# relays2.net
KiCad netlist of a schematic drawn in Altium Designer
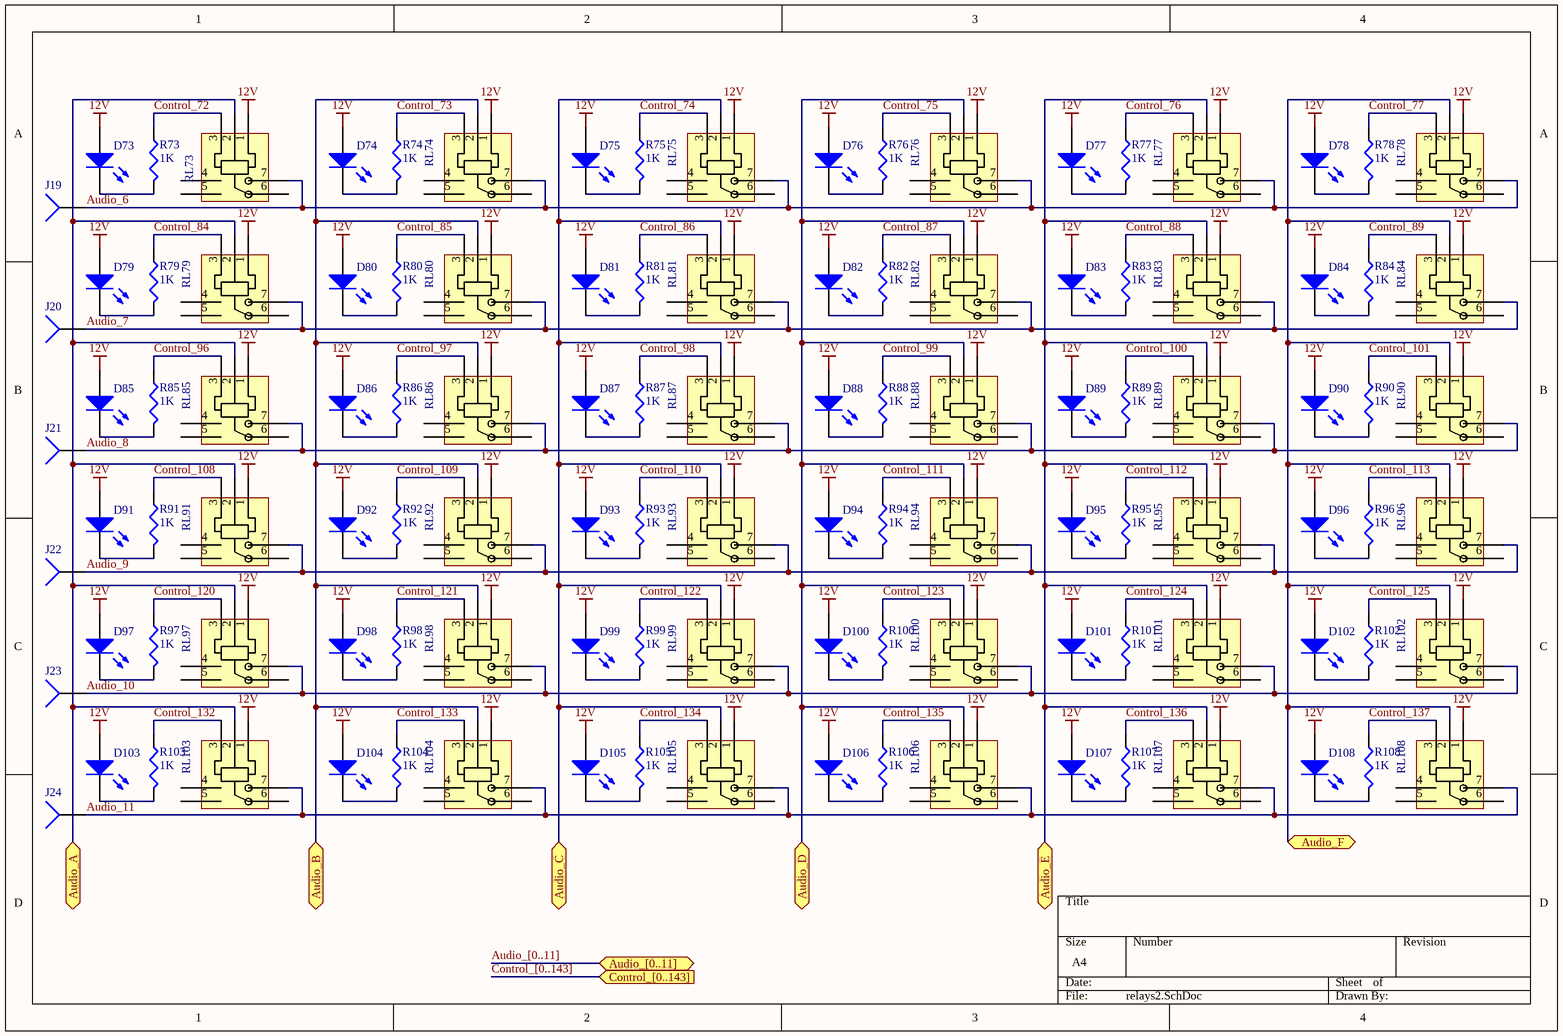
[diagram p0: relays2.SchDoc]

(export (version "E")
  (design (tool "Eeschema 10.0.6"))
  (components
    (comp (ref "D73")
      (value "LED0")
      (footprint "LED_round_5mm")
      (description "Typical INFRARED GaAs LED")
      (libsource (lib "Miscellaneous Devices") (part "LED0"))
    )
    (comp (ref "D74")
      (value "LED0")
      (footprint "LED_round_5mm")
      (description "Typical INFRARED GaAs LED")
      (libsource (lib "Miscellaneous Devices") (part "LED0"))
    )
    (comp (ref "D75")
      (value "LED0")
      (footprint "LED_round_5mm")
      (description "Typical INFRARED GaAs LED")
      (libsource (lib "Miscellaneous Devices") (part "LED0"))
    )
    (comp (ref "D76")
      (value "LED0")
      (footprint "LED_round_5mm")
      (description "Typical INFRARED GaAs LED")
      (libsource (lib "Miscellaneous Devices") (part "LED0"))
    )
    (comp (ref "D77")
      (value "LED0")
      (footprint "LED_round_5mm")
      (description "Typical INFRARED GaAs LED")
      (libsource (lib "Miscellaneous Devices") (part "LED0"))
    )
    (comp (ref "D78")
      (value "LED0")
      (footprint "LED_round_5mm")
      (description "Typical INFRARED GaAs LED")
      (libsource (lib "Miscellaneous Devices") (part "LED0"))
    )
    (comp (ref "D79")
      (value "LED0")
      (footprint "LED_round_5mm")
      (description "Typical INFRARED GaAs LED")
      (libsource (lib "Miscellaneous Devices") (part "LED0"))
    )
    (comp (ref "D80")
      (value "LED0")
      (footprint "LED_round_5mm")
      (description "Typical INFRARED GaAs LED")
      (libsource (lib "Miscellaneous Devices") (part "LED0"))
    )
    (comp (ref "D81")
      (value "LED0")
      (footprint "LED_round_5mm")
      (description "Typical INFRARED GaAs LED")
      (libsource (lib "Miscellaneous Devices") (part "LED0"))
    )
    (comp (ref "D82")
      (value "LED0")
      (footprint "LED_round_5mm")
      (description "Typical INFRARED GaAs LED")
      (libsource (lib "Miscellaneous Devices") (part "LED0"))
    )
    (comp (ref "D83")
      (value "LED0")
      (footprint "LED_round_5mm")
      (description "Typical INFRARED GaAs LED")
      (libsource (lib "Miscellaneous Devices") (part "LED0"))
    )
    (comp (ref "D84")
      (value "LED0")
      (footprint "LED_round_5mm")
      (description "Typical INFRARED GaAs LED")
      (libsource (lib "Miscellaneous Devices") (part "LED0"))
    )
    (comp (ref "D85")
      (value "LED0")
      (footprint "LED_round_5mm")
      (description "Typical INFRARED GaAs LED")
      (libsource (lib "Miscellaneous Devices") (part "LED0"))
    )
    (comp (ref "D86")
      (value "LED0")
      (footprint "LED_round_5mm")
      (description "Typical INFRARED GaAs LED")
      (libsource (lib "Miscellaneous Devices") (part "LED0"))
    )
    (comp (ref "D87")
      (value "LED0")
      (footprint "LED_round_5mm")
      (description "Typical INFRARED GaAs LED")
      (libsource (lib "Miscellaneous Devices") (part "LED0"))
    )
    (comp (ref "D88")
      (value "LED0")
      (footprint "LED_round_5mm")
      (description "Typical INFRARED GaAs LED")
      (libsource (lib "Miscellaneous Devices") (part "LED0"))
    )
    (comp (ref "D89")
      (value "LED0")
      (footprint "LED_round_5mm")
      (description "Typical INFRARED GaAs LED")
      (libsource (lib "Miscellaneous Devices") (part "LED0"))
    )
    (comp (ref "D90")
      (value "LED0")
      (footprint "LED_round_5mm")
      (description "Typical INFRARED GaAs LED")
      (libsource (lib "Miscellaneous Devices") (part "LED0"))
    )
    (comp (ref "D91")
      (value "LED0")
      (footprint "LED_round_5mm")
      (description "Typical INFRARED GaAs LED")
      (libsource (lib "Miscellaneous Devices") (part "LED0"))
    )
    (comp (ref "D92")
      (value "LED0")
      (footprint "LED_round_5mm")
      (description "Typical INFRARED GaAs LED")
      (libsource (lib "Miscellaneous Devices") (part "LED0"))
    )
    (comp (ref "D93")
      (value "LED0")
      (footprint "LED_round_5mm")
      (description "Typical INFRARED GaAs LED")
      (libsource (lib "Miscellaneous Devices") (part "LED0"))
    )
    (comp (ref "D94")
      (value "LED0")
      (footprint "LED_round_5mm")
      (description "Typical INFRARED GaAs LED")
      (libsource (lib "Miscellaneous Devices") (part "LED0"))
    )
    (comp (ref "D95")
      (value "LED0")
      (footprint "LED_round_5mm")
      (description "Typical INFRARED GaAs LED")
      (libsource (lib "Miscellaneous Devices") (part "LED0"))
    )
    (comp (ref "D96")
      (value "LED0")
      (footprint "LED_round_5mm")
      (description "Typical INFRARED GaAs LED")
      (libsource (lib "Miscellaneous Devices") (part "LED0"))
    )
    (comp (ref "D97")
      (value "LED0")
      (footprint "LED_round_5mm")
      (description "Typical INFRARED GaAs LED")
      (libsource (lib "Miscellaneous Devices") (part "LED0"))
    )
    (comp (ref "D98")
      (value "LED0")
      (footprint "LED_round_5mm")
      (description "Typical INFRARED GaAs LED")
      (libsource (lib "Miscellaneous Devices") (part "LED0"))
    )
    (comp (ref "D99")
      (value "LED0")
      (footprint "LED_round_5mm")
      (description "Typical INFRARED GaAs LED")
      (libsource (lib "Miscellaneous Devices") (part "LED0"))
    )
    (comp (ref "D100")
      (value "LED0")
      (footprint "LED_round_5mm")
      (description "Typical INFRARED GaAs LED")
      (libsource (lib "Miscellaneous Devices") (part "LED0"))
    )
    (comp (ref "D101")
      (value "LED0")
      (footprint "LED_round_5mm")
      (description "Typical INFRARED GaAs LED")
      (libsource (lib "Miscellaneous Devices") (part "LED0"))
    )
    (comp (ref "D102")
      (value "LED0")
      (footprint "LED_round_5mm")
      (description "Typical INFRARED GaAs LED")
      (libsource (lib "Miscellaneous Devices") (part "LED0"))
    )
    (comp (ref "D103")
      (value "LED0")
      (footprint "LED_round_5mm")
      (description "Typical INFRARED GaAs LED")
      (libsource (lib "Miscellaneous Devices") (part "LED0"))
    )
    (comp (ref "D104")
      (value "LED0")
      (footprint "LED_round_5mm")
      (description "Typical INFRARED GaAs LED")
      (libsource (lib "Miscellaneous Devices") (part "LED0"))
    )
    (comp (ref "D105")
      (value "LED0")
      (footprint "LED_round_5mm")
      (description "Typical INFRARED GaAs LED")
      (libsource (lib "Miscellaneous Devices") (part "LED0"))
    )
    (comp (ref "D106")
      (value "LED0")
      (footprint "LED_round_5mm")
      (description "Typical INFRARED GaAs LED")
      (libsource (lib "Miscellaneous Devices") (part "LED0"))
    )
    (comp (ref "D107")
      (value "LED0")
      (footprint "LED_round_5mm")
      (description "Typical INFRARED GaAs LED")
      (libsource (lib "Miscellaneous Devices") (part "LED0"))
    )
    (comp (ref "D108")
      (value "LED0")
      (footprint "LED_round_5mm")
      (description "Typical INFRARED GaAs LED")
      (libsource (lib "Miscellaneous Devices") (part "LED0"))
    )
    (comp (ref "J19")
      (value "Audio")
      (footprint "Conn_1_2x4")
      (description "Socket")
      (libsource (lib "Miscellaneous Connectors") (part "Socket"))
    )
    (comp (ref "J20")
      (value "Audio")
      (footprint "Conn_1_2x4")
      (description "Socket")
      (libsource (lib "Miscellaneous Connectors") (part "Socket"))
    )
    (comp (ref "J21")
      (value "Audio")
      (footprint "Conn_1_2x4")
      (description "Socket")
      (libsource (lib "Miscellaneous Connectors") (part "Socket"))
    )
    (comp (ref "J22")
      (value "Audio")
      (footprint "Conn_1_2x4")
      (description "Socket")
      (libsource (lib "Miscellaneous Connectors") (part "Socket"))
    )
    (comp (ref "J23")
      (value "Audio")
      (footprint "Conn_1_2x4")
      (description "Socket")
      (libsource (lib "Miscellaneous Connectors") (part "Socket"))
    )
    (comp (ref "J24")
      (value "Audio")
      (footprint "Conn_1_2x4")
      (description "Socket")
      (libsource (lib "Miscellaneous Connectors") (part "Socket"))
    )
    (comp (ref "R73")
      (value "1K")
      (footprint "J1-0603")
      (description "Resistor")
      (fields (field (name "Comment") "Res3"))
      (libsource (lib "Miscellaneous Devices") (part "Res3"))
    )
    (comp (ref "R74")
      (value "1K")
      (footprint "J1-0603")
      (description "Resistor")
      (fields (field (name "Comment") "Res3"))
      (libsource (lib "Miscellaneous Devices") (part "Res3"))
    )
    (comp (ref "R75")
      (value "1K")
      (footprint "J1-0603")
      (description "Resistor")
      (fields (field (name "Comment") "Res3"))
      (libsource (lib "Miscellaneous Devices") (part "Res3"))
    )
    (comp (ref "R76")
      (value "1K")
      (footprint "J1-0603")
      (description "Resistor")
      (fields (field (name "Comment") "Res3"))
      (libsource (lib "Miscellaneous Devices") (part "Res3"))
    )
    (comp (ref "R77")
      (value "1K")
      (footprint "J1-0603")
      (description "Resistor")
      (fields (field (name "Comment") "Res3"))
      (libsource (lib "Miscellaneous Devices") (part "Res3"))
    )
    (comp (ref "R78")
      (value "1K")
      (footprint "J1-0603")
      (description "Resistor")
      (fields (field (name "Comment") "Res3"))
      (libsource (lib "Miscellaneous Devices") (part "Res3"))
    )
    (comp (ref "R79")
      (value "1K")
      (footprint "J1-0603")
      (description "Resistor")
      (fields (field (name "Comment") "Res3"))
      (libsource (lib "Miscellaneous Devices") (part "Res3"))
    )
    (comp (ref "R80")
      (value "1K")
      (footprint "J1-0603")
      (description "Resistor")
      (fields (field (name "Comment") "Res3"))
      (libsource (lib "Miscellaneous Devices") (part "Res3"))
    )
    (comp (ref "R81")
      (value "1K")
      (footprint "J1-0603")
      (description "Resistor")
      (fields (field (name "Comment") "Res3"))
      (libsource (lib "Miscellaneous Devices") (part "Res3"))
    )
    (comp (ref "R82")
      (value "1K")
      (footprint "J1-0603")
      (description "Resistor")
      (fields (field (name "Comment") "Res3"))
      (libsource (lib "Miscellaneous Devices") (part "Res3"))
    )
    (comp (ref "R83")
      (value "1K")
      (footprint "J1-0603")
      (description "Resistor")
      (fields (field (name "Comment") "Res3"))
      (libsource (lib "Miscellaneous Devices") (part "Res3"))
    )
    (comp (ref "R84")
      (value "1K")
      (footprint "J1-0603")
      (description "Resistor")
      (fields (field (name "Comment") "Res3"))
      (libsource (lib "Miscellaneous Devices") (part "Res3"))
    )
    (comp (ref "R85")
      (value "1K")
      (footprint "J1-0603")
      (description "Resistor")
      (fields (field (name "Comment") "Res3"))
      (libsource (lib "Miscellaneous Devices") (part "Res3"))
    )
    (comp (ref "R86")
      (value "1K")
      (footprint "J1-0603")
      (description "Resistor")
      (fields (field (name "Comment") "Res3"))
      (libsource (lib "Miscellaneous Devices") (part "Res3"))
    )
    (comp (ref "R87")
      (value "1K")
      (footprint "J1-0603")
      (description "Resistor")
      (fields (field (name "Comment") "Res3"))
      (libsource (lib "Miscellaneous Devices") (part "Res3"))
    )
    (comp (ref "R88")
      (value "1K")
      (footprint "J1-0603")
      (description "Resistor")
      (fields (field (name "Comment") "Res3"))
      (libsource (lib "Miscellaneous Devices") (part "Res3"))
    )
    (comp (ref "R89")
      (value "1K")
      (footprint "J1-0603")
      (description "Resistor")
      (fields (field (name "Comment") "Res3"))
      (libsource (lib "Miscellaneous Devices") (part "Res3"))
    )
    (comp (ref "R90")
      (value "1K")
      (footprint "J1-0603")
      (description "Resistor")
      (fields (field (name "Comment") "Res3"))
      (libsource (lib "Miscellaneous Devices") (part "Res3"))
    )
    (comp (ref "R91")
      (value "1K")
      (footprint "J1-0603")
      (description "Resistor")
      (fields (field (name "Comment") "Res3"))
      (libsource (lib "Miscellaneous Devices") (part "Res3"))
    )
    (comp (ref "R92")
      (value "1K")
      (footprint "J1-0603")
      (description "Resistor")
      (fields (field (name "Comment") "Res3"))
      (libsource (lib "Miscellaneous Devices") (part "Res3"))
    )
    (comp (ref "R93")
      (value "1K")
      (footprint "J1-0603")
      (description "Resistor")
      (fields (field (name "Comment") "Res3"))
      (libsource (lib "Miscellaneous Devices") (part "Res3"))
    )
    (comp (ref "R94")
      (value "1K")
      (footprint "J1-0603")
      (description "Resistor")
      (fields (field (name "Comment") "Res3"))
      (libsource (lib "Miscellaneous Devices") (part "Res3"))
    )
    (comp (ref "R95")
      (value "1K")
      (footprint "J1-0603")
      (description "Resistor")
      (fields (field (name "Comment") "Res3"))
      (libsource (lib "Miscellaneous Devices") (part "Res3"))
    )
    (comp (ref "R96")
      (value "1K")
      (footprint "J1-0603")
      (description "Resistor")
      (fields (field (name "Comment") "Res3"))
      (libsource (lib "Miscellaneous Devices") (part "Res3"))
    )
    (comp (ref "R97")
      (value "1K")
      (footprint "J1-0603")
      (description "Resistor")
      (fields (field (name "Comment") "Res3"))
      (libsource (lib "Miscellaneous Devices") (part "Res3"))
    )
    (comp (ref "R98")
      (value "1K")
      (footprint "J1-0603")
      (description "Resistor")
      (fields (field (name "Comment") "Res3"))
      (libsource (lib "Miscellaneous Devices") (part "Res3"))
    )
    (comp (ref "R99")
      (value "1K")
      (footprint "J1-0603")
      (description "Resistor")
      (fields (field (name "Comment") "Res3"))
      (libsource (lib "Miscellaneous Devices") (part "Res3"))
    )
    (comp (ref "R100")
      (value "1K")
      (footprint "J1-0603")
      (description "Resistor")
      (fields (field (name "Comment") "Res3"))
      (libsource (lib "Miscellaneous Devices") (part "Res3"))
    )
    (comp (ref "R101")
      (value "1K")
      (footprint "J1-0603")
      (description "Resistor")
      (fields (field (name "Comment") "Res3"))
      (libsource (lib "Miscellaneous Devices") (part "Res3"))
    )
    (comp (ref "R102")
      (value "1K")
      (footprint "J1-0603")
      (description "Resistor")
      (fields (field (name "Comment") "Res3"))
      (libsource (lib "Miscellaneous Devices") (part "Res3"))
    )
    (comp (ref "R103")
      (value "1K")
      (footprint "J1-0603")
      (description "Resistor")
      (fields (field (name "Comment") "Res3"))
      (libsource (lib "Miscellaneous Devices") (part "Res3"))
    )
    (comp (ref "R104")
      (value "1K")
      (footprint "J1-0603")
      (description "Resistor")
      (fields (field (name "Comment") "Res3"))
      (libsource (lib "Miscellaneous Devices") (part "Res3"))
    )
    (comp (ref "R105")
      (value "1K")
      (footprint "J1-0603")
      (description "Resistor")
      (fields (field (name "Comment") "Res3"))
      (libsource (lib "Miscellaneous Devices") (part "Res3"))
    )
    (comp (ref "R106")
      (value "1K")
      (footprint "J1-0603")
      (description "Resistor")
      (fields (field (name "Comment") "Res3"))
      (libsource (lib "Miscellaneous Devices") (part "Res3"))
    )
    (comp (ref "R107")
      (value "1K")
      (footprint "J1-0603")
      (description "Resistor")
      (fields (field (name "Comment") "Res3"))
      (libsource (lib "Miscellaneous Devices") (part "Res3"))
    )
    (comp (ref "R108")
      (value "1K")
      (footprint "J1-0603")
      (description "Resistor")
      (fields (field (name "Comment") "Res3"))
      (libsource (lib "Miscellaneous Devices") (part "Res3"))
    )
    (comp (ref "RL73")
      (value "Relay")
      (footprint "Relay_FRA3")
      (description "Miniature power relay")
      (fields (field (name "PART NUMBER") "FRA3C-DC12"))
      (libsource (lib "tech-thing") (part "Relay_FRA3"))
    )
    (comp (ref "RL74")
      (value "Relay")
      (footprint "Relay_FRA3")
      (description "Miniature power relay")
      (fields (field (name "PART NUMBER") "FRA3C-DC12"))
      (libsource (lib "tech-thing") (part "Relay_FRA3"))
    )
    (comp (ref "RL75")
      (value "Relay")
      (footprint "Relay_FRA3")
      (description "Miniature power relay")
      (fields (field (name "PART NUMBER") "FRA3C-DC12"))
      (libsource (lib "tech-thing") (part "Relay_FRA3"))
    )
    (comp (ref "RL76")
      (value "Relay")
      (footprint "Relay_FRA3")
      (description "Miniature power relay")
      (fields (field (name "PART NUMBER") "FRA3C-DC12"))
      (libsource (lib "tech-thing") (part "Relay_FRA3"))
    )
    (comp (ref "RL77")
      (value "Relay")
      (footprint "Relay_FRA3")
      (description "Miniature power relay")
      (fields (field (name "PART NUMBER") "FRA3C-DC12"))
      (libsource (lib "tech-thing") (part "Relay_FRA3"))
    )
    (comp (ref "RL78")
      (value "Relay")
      (footprint "Relay_FRA3")
      (description "Miniature power relay")
      (fields (field (name "PART NUMBER") "FRA3C-DC12"))
      (libsource (lib "tech-thing") (part "Relay_FRA3"))
    )
    (comp (ref "RL79")
      (value "Relay")
      (footprint "Relay_FRA3")
      (description "Miniature power relay")
      (fields (field (name "PART NUMBER") "FRA3C-DC12"))
      (libsource (lib "tech-thing") (part "Relay_FRA3"))
    )
    (comp (ref "RL80")
      (value "Relay")
      (footprint "Relay_FRA3")
      (description "Miniature power relay")
      (fields (field (name "PART NUMBER") "FRA3C-DC12"))
      (libsource (lib "tech-thing") (part "Relay_FRA3"))
    )
    (comp (ref "RL81")
      (value "Relay")
      (footprint "Relay_FRA3")
      (description "Miniature power relay")
      (fields (field (name "PART NUMBER") "FRA3C-DC12"))
      (libsource (lib "tech-thing") (part "Relay_FRA3"))
    )
    (comp (ref "RL82")
      (value "Relay")
      (footprint "Relay_FRA3")
      (description "Miniature power relay")
      (fields (field (name "PART NUMBER") "FRA3C-DC12"))
      (libsource (lib "tech-thing") (part "Relay_FRA3"))
    )
    (comp (ref "RL83")
      (value "Relay")
      (footprint "Relay_FRA3")
      (description "Miniature power relay")
      (fields (field (name "PART NUMBER") "FRA3C-DC12"))
      (libsource (lib "tech-thing") (part "Relay_FRA3"))
    )
    (comp (ref "RL84")
      (value "Relay")
      (footprint "Relay_FRA3")
      (description "Miniature power relay")
      (fields (field (name "PART NUMBER") "FRA3C-DC12"))
      (libsource (lib "tech-thing") (part "Relay_FRA3"))
    )
    (comp (ref "RL85")
      (value "Relay")
      (footprint "Relay_FRA3")
      (description "Miniature power relay")
      (fields (field (name "PART NUMBER") "FRA3C-DC12"))
      (libsource (lib "tech-thing") (part "Relay_FRA3"))
    )
    (comp (ref "RL86")
      (value "Relay")
      (footprint "Relay_FRA3")
      (description "Miniature power relay")
      (fields (field (name "PART NUMBER") "FRA3C-DC12"))
      (libsource (lib "tech-thing") (part "Relay_FRA3"))
    )
    (comp (ref "RL87")
      (value "Relay")
      (footprint "Relay_FRA3")
      (description "Miniature power relay")
      (fields (field (name "PART NUMBER") "FRA3C-DC12"))
      (libsource (lib "tech-thing") (part "Relay_FRA3"))
    )
    (comp (ref "RL88")
      (value "Relay")
      (footprint "Relay_FRA3")
      (description "Miniature power relay")
      (fields (field (name "PART NUMBER") "FRA3C-DC12"))
      (libsource (lib "tech-thing") (part "Relay_FRA3"))
    )
    (comp (ref "RL89")
      (value "Relay")
      (footprint "Relay_FRA3")
      (description "Miniature power relay")
      (fields (field (name "PART NUMBER") "FRA3C-DC12"))
      (libsource (lib "tech-thing") (part "Relay_FRA3"))
    )
    (comp (ref "RL90")
      (value "Relay")
      (footprint "Relay_FRA3")
      (description "Miniature power relay")
      (fields (field (name "PART NUMBER") "FRA3C-DC12"))
      (libsource (lib "tech-thing") (part "Relay_FRA3"))
    )
    (comp (ref "RL91")
      (value "Relay")
      (footprint "Relay_FRA3")
      (description "Miniature power relay")
      (fields (field (name "PART NUMBER") "FRA3C-DC12"))
      (libsource (lib "tech-thing") (part "Relay_FRA3"))
    )
    (comp (ref "RL92")
      (value "Relay")
      (footprint "Relay_FRA3")
      (description "Miniature power relay")
      (fields (field (name "PART NUMBER") "FRA3C-DC12"))
      (libsource (lib "tech-thing") (part "Relay_FRA3"))
    )
    (comp (ref "RL93")
      (value "Relay")
      (footprint "Relay_FRA3")
      (description "Miniature power relay")
      (fields (field (name "PART NUMBER") "FRA3C-DC12"))
      (libsource (lib "tech-thing") (part "Relay_FRA3"))
    )
    (comp (ref "RL94")
      (value "Relay")
      (footprint "Relay_FRA3")
      (description "Miniature power relay")
      (fields (field (name "PART NUMBER") "FRA3C-DC12"))
      (libsource (lib "tech-thing") (part "Relay_FRA3"))
    )
    (comp (ref "RL95")
      (value "Relay")
      (footprint "Relay_FRA3")
      (description "Miniature power relay")
      (fields (field (name "PART NUMBER") "FRA3C-DC12"))
      (libsource (lib "tech-thing") (part "Relay_FRA3"))
    )
    (comp (ref "RL96")
      (value "Relay")
      (footprint "Relay_FRA3")
      (description "Miniature power relay")
      (fields (field (name "PART NUMBER") "FRA3C-DC12"))
      (libsource (lib "tech-thing") (part "Relay_FRA3"))
    )
    (comp (ref "RL97")
      (value "Relay")
      (footprint "Relay_FRA3")
      (description "Miniature power relay")
      (fields (field (name "PART NUMBER") "FRA3C-DC12"))
      (libsource (lib "tech-thing") (part "Relay_FRA3"))
    )
    (comp (ref "RL98")
      (value "Relay")
      (footprint "Relay_FRA3")
      (description "Miniature power relay")
      (fields (field (name "PART NUMBER") "FRA3C-DC12"))
      (libsource (lib "tech-thing") (part "Relay_FRA3"))
    )
    (comp (ref "RL99")
      (value "Relay")
      (footprint "Relay_FRA3")
      (description "Miniature power relay")
      (fields (field (name "PART NUMBER") "FRA3C-DC12"))
      (libsource (lib "tech-thing") (part "Relay_FRA3"))
    )
    (comp (ref "RL100")
      (value "Relay")
      (footprint "Relay_FRA3")
      (description "Miniature power relay")
      (fields (field (name "PART NUMBER") "FRA3C-DC12"))
      (libsource (lib "tech-thing") (part "Relay_FRA3"))
    )
    (comp (ref "RL101")
      (value "Relay")
      (footprint "Relay_FRA3")
      (description "Miniature power relay")
      (fields (field (name "PART NUMBER") "FRA3C-DC12"))
      (libsource (lib "tech-thing") (part "Relay_FRA3"))
    )
    (comp (ref "RL102")
      (value "Relay")
      (footprint "Relay_FRA3")
      (description "Miniature power relay")
      (fields (field (name "PART NUMBER") "FRA3C-DC12"))
      (libsource (lib "tech-thing") (part "Relay_FRA3"))
    )
    (comp (ref "RL103")
      (value "Relay")
      (footprint "Relay_FRA3")
      (description "Miniature power relay")
      (fields (field (name "PART NUMBER") "FRA3C-DC12"))
      (libsource (lib "tech-thing") (part "Relay_FRA3"))
    )
    (comp (ref "RL104")
      (value "Relay")
      (footprint "Relay_FRA3")
      (description "Miniature power relay")
      (fields (field (name "PART NUMBER") "FRA3C-DC12"))
      (libsource (lib "tech-thing") (part "Relay_FRA3"))
    )
    (comp (ref "RL105")
      (value "Relay")
      (footprint "Relay_FRA3")
      (description "Miniature power relay")
      (fields (field (name "PART NUMBER") "FRA3C-DC12"))
      (libsource (lib "tech-thing") (part "Relay_FRA3"))
    )
    (comp (ref "RL106")
      (value "Relay")
      (footprint "Relay_FRA3")
      (description "Miniature power relay")
      (fields (field (name "PART NUMBER") "FRA3C-DC12"))
      (libsource (lib "tech-thing") (part "Relay_FRA3"))
    )
    (comp (ref "RL107")
      (value "Relay")
      (footprint "Relay_FRA3")
      (description "Miniature power relay")
      (fields (field (name "PART NUMBER") "FRA3C-DC12"))
      (libsource (lib "tech-thing") (part "Relay_FRA3"))
    )
    (comp (ref "RL108")
      (value "Relay")
      (footprint "Relay_FRA3")
      (description "Miniature power relay")
      (fields (field (name "PART NUMBER") "FRA3C-DC12"))
      (libsource (lib "tech-thing") (part "Relay_FRA3"))
    )
  )
  (nets
    (net (code "115") (name "/Audio_6") (class "Default")
      (node (ref "J19") (pin "1") (pinfunction "1_1") (pintype "passive"))
      (node (ref "RL73") (pin "7") (pintype "passive"))
      (node (ref "RL74") (pin "7") (pintype "passive"))
      (node (ref "RL75") (pin "7") (pintype "passive"))
      (node (ref "RL76") (pin "7") (pintype "passive"))
      (node (ref "RL77") (pin "7") (pintype "passive"))
      (node (ref "RL78") (pin "7") (pintype "passive"))
    )
    (net (code "116") (name "/Audio_7") (class "Default")
      (node (ref "J20") (pin "1") (pinfunction "1_1") (pintype "passive"))
      (node (ref "RL79") (pin "7") (pintype "passive"))
      (node (ref "RL80") (pin "7") (pintype "passive"))
      (node (ref "RL81") (pin "7") (pintype "passive"))
      (node (ref "RL82") (pin "7") (pintype "passive"))
      (node (ref "RL83") (pin "7") (pintype "passive"))
      (node (ref "RL84") (pin "7") (pintype "passive"))
    )
    (net (code "117") (name "/Audio_8") (class "Default")
      (node (ref "J21") (pin "1") (pinfunction "1_1") (pintype "passive"))
      (node (ref "RL85") (pin "7") (pintype "passive"))
      (node (ref "RL86") (pin "7") (pintype "passive"))
      (node (ref "RL87") (pin "7") (pintype "passive"))
      (node (ref "RL88") (pin "7") (pintype "passive"))
      (node (ref "RL89") (pin "7") (pintype "passive"))
      (node (ref "RL90") (pin "7") (pintype "passive"))
    )
    (net (code "118") (name "/Audio_9") (class "Default")
      (node (ref "J22") (pin "1") (pinfunction "1_1") (pintype "passive"))
      (node (ref "RL91") (pin "7") (pintype "passive"))
      (node (ref "RL92") (pin "7") (pintype "passive"))
      (node (ref "RL93") (pin "7") (pintype "passive"))
      (node (ref "RL94") (pin "7") (pintype "passive"))
      (node (ref "RL95") (pin "7") (pintype "passive"))
      (node (ref "RL96") (pin "7") (pintype "passive"))
    )
    (net (code "119") (name "/Audio_10") (class "Default")
      (node (ref "J23") (pin "1") (pinfunction "1_1") (pintype "passive"))
      (node (ref "RL100") (pin "7") (pintype "passive"))
      (node (ref "RL101") (pin "7") (pintype "passive"))
      (node (ref "RL102") (pin "7") (pintype "passive"))
      (node (ref "RL97") (pin "7") (pintype "passive"))
      (node (ref "RL98") (pin "7") (pintype "passive"))
      (node (ref "RL99") (pin "7") (pintype "passive"))
    )
    (net (code "120") (name "/Audio_11") (class "Default")
      (node (ref "J24") (pin "1") (pinfunction "1_1") (pintype "passive"))
      (node (ref "RL103") (pin "7") (pintype "passive"))
      (node (ref "RL104") (pin "7") (pintype "passive"))
      (node (ref "RL105") (pin "7") (pintype "passive"))
      (node (ref "RL106") (pin "7") (pintype "passive"))
      (node (ref "RL107") (pin "7") (pintype "passive"))
      (node (ref "RL108") (pin "7") (pintype "passive"))
    )
    (net (code "121") (name "/Audio_A") (class "Default")
      (node (ref "RL103") (pin "2") (pintype "passive"))
      (node (ref "RL73") (pin "2") (pintype "passive"))
      (node (ref "RL79") (pin "2") (pintype "passive"))
      (node (ref "RL85") (pin "2") (pintype "passive"))
      (node (ref "RL91") (pin "2") (pintype "passive"))
      (node (ref "RL97") (pin "2") (pintype "passive"))
    )
    (net (code "122") (name "/Audio_B") (class "Default")
      (node (ref "RL104") (pin "2") (pintype "passive"))
      (node (ref "RL74") (pin "2") (pintype "passive"))
      (node (ref "RL80") (pin "2") (pintype "passive"))
      (node (ref "RL86") (pin "2") (pintype "passive"))
      (node (ref "RL92") (pin "2") (pintype "passive"))
      (node (ref "RL98") (pin "2") (pintype "passive"))
    )
    (net (code "123") (name "/Audio_C") (class "Default")
      (node (ref "RL105") (pin "2") (pintype "passive"))
      (node (ref "RL75") (pin "2") (pintype "passive"))
      (node (ref "RL81") (pin "2") (pintype "passive"))
      (node (ref "RL87") (pin "2") (pintype "passive"))
      (node (ref "RL93") (pin "2") (pintype "passive"))
      (node (ref "RL99") (pin "2") (pintype "passive"))
    )
    (net (code "124") (name "/Audio_D") (class "Default")
      (node (ref "RL100") (pin "2") (pintype "passive"))
      (node (ref "RL106") (pin "2") (pintype "passive"))
      (node (ref "RL76") (pin "2") (pintype "passive"))
      (node (ref "RL82") (pin "2") (pintype "passive"))
      (node (ref "RL88") (pin "2") (pintype "passive"))
      (node (ref "RL94") (pin "2") (pintype "passive"))
    )
    (net (code "125") (name "/Audio_E") (class "Default")
      (node (ref "RL101") (pin "2") (pintype "passive"))
      (node (ref "RL107") (pin "2") (pintype "passive"))
      (node (ref "RL77") (pin "2") (pintype "passive"))
      (node (ref "RL83") (pin "2") (pintype "passive"))
      (node (ref "RL89") (pin "2") (pintype "passive"))
      (node (ref "RL95") (pin "2") (pintype "passive"))
    )
    (net (code "126") (name "/Audio_F") (class "Default")
      (node (ref "RL102") (pin "2") (pintype "passive"))
      (node (ref "RL108") (pin "2") (pintype "passive"))
      (node (ref "RL78") (pin "2") (pintype "passive"))
      (node (ref "RL84") (pin "2") (pintype "passive"))
      (node (ref "RL90") (pin "2") (pintype "passive"))
      (node (ref "RL96") (pin "2") (pintype "passive"))
    )
    (net (code "128") (name "/Control_72") (class "Default")
      (node (ref "R73") (pin "1") (pinfunction "1_1") (pintype "passive"))
      (node (ref "RL73") (pin "3") (pintype "passive"))
    )
    (net (code "129") (name "/Control_73") (class "Default")
      (node (ref "R74") (pin "1") (pinfunction "1_1") (pintype "passive"))
      (node (ref "RL74") (pin "3") (pintype "passive"))
    )
    (net (code "130") (name "/Control_74") (class "Default")
      (node (ref "R75") (pin "1") (pinfunction "1_1") (pintype "passive"))
      (node (ref "RL75") (pin "3") (pintype "passive"))
    )
    (net (code "131") (name "/Control_75") (class "Default")
      (node (ref "R76") (pin "1") (pinfunction "1_1") (pintype "passive"))
      (node (ref "RL76") (pin "3") (pintype "passive"))
    )
    (net (code "132") (name "/Control_76") (class "Default")
      (node (ref "R77") (pin "1") (pinfunction "1_1") (pintype "passive"))
      (node (ref "RL77") (pin "3") (pintype "passive"))
    )
    (net (code "133") (name "/Control_77") (class "Default")
      (node (ref "R78") (pin "1") (pinfunction "1_1") (pintype "passive"))
      (node (ref "RL78") (pin "3") (pintype "passive"))
    )
    (net (code "134") (name "/Control_84") (class "Default")
      (node (ref "R79") (pin "1") (pinfunction "1_1") (pintype "passive"))
      (node (ref "RL79") (pin "3") (pintype "passive"))
    )
    (net (code "135") (name "/Control_85") (class "Default")
      (node (ref "R80") (pin "1") (pinfunction "1_1") (pintype "passive"))
      (node (ref "RL80") (pin "3") (pintype "passive"))
    )
    (net (code "136") (name "/Control_86") (class "Default")
      (node (ref "R81") (pin "1") (pinfunction "1_1") (pintype "passive"))
      (node (ref "RL81") (pin "3") (pintype "passive"))
    )
    (net (code "137") (name "/Control_87") (class "Default")
      (node (ref "R82") (pin "1") (pinfunction "1_1") (pintype "passive"))
      (node (ref "RL82") (pin "3") (pintype "passive"))
    )
    (net (code "138") (name "/Control_88") (class "Default")
      (node (ref "R83") (pin "1") (pinfunction "1_1") (pintype "passive"))
      (node (ref "RL83") (pin "3") (pintype "passive"))
    )
    (net (code "139") (name "/Control_89") (class "Default")
      (node (ref "R84") (pin "1") (pinfunction "1_1") (pintype "passive"))
      (node (ref "RL84") (pin "3") (pintype "passive"))
    )
    (net (code "140") (name "/Control_96") (class "Default")
      (node (ref "R85") (pin "1") (pinfunction "1_1") (pintype "passive"))
      (node (ref "RL85") (pin "3") (pintype "passive"))
    )
    (net (code "141") (name "/Control_97") (class "Default")
      (node (ref "R86") (pin "1") (pinfunction "1_1") (pintype "passive"))
      (node (ref "RL86") (pin "3") (pintype "passive"))
    )
    (net (code "142") (name "/Control_98") (class "Default")
      (node (ref "R87") (pin "1") (pinfunction "1_1") (pintype "passive"))
      (node (ref "RL87") (pin "3") (pintype "passive"))
    )
    (net (code "143") (name "/Control_99") (class "Default")
      (node (ref "R88") (pin "1") (pinfunction "1_1") (pintype "passive"))
      (node (ref "RL88") (pin "3") (pintype "passive"))
    )
    (net (code "144") (name "/Control_100") (class "Default")
      (node (ref "R89") (pin "1") (pinfunction "1_1") (pintype "passive"))
      (node (ref "RL89") (pin "3") (pintype "passive"))
    )
    (net (code "145") (name "/Control_101") (class "Default")
      (node (ref "R90") (pin "1") (pinfunction "1_1") (pintype "passive"))
      (node (ref "RL90") (pin "3") (pintype "passive"))
    )
    (net (code "146") (name "/Control_108") (class "Default")
      (node (ref "R91") (pin "1") (pinfunction "1_1") (pintype "passive"))
      (node (ref "RL91") (pin "3") (pintype "passive"))
    )
    (net (code "147") (name "/Control_109") (class "Default")
      (node (ref "R92") (pin "1") (pinfunction "1_1") (pintype "passive"))
      (node (ref "RL92") (pin "3") (pintype "passive"))
    )
    (net (code "148") (name "/Control_110") (class "Default")
      (node (ref "R93") (pin "1") (pinfunction "1_1") (pintype "passive"))
      (node (ref "RL93") (pin "3") (pintype "passive"))
    )
    (net (code "149") (name "/Control_111") (class "Default")
      (node (ref "R94") (pin "1") (pinfunction "1_1") (pintype "passive"))
      (node (ref "RL94") (pin "3") (pintype "passive"))
    )
    (net (code "150") (name "/Control_112") (class "Default")
      (node (ref "R95") (pin "1") (pinfunction "1_1") (pintype "passive"))
      (node (ref "RL95") (pin "3") (pintype "passive"))
    )
    (net (code "151") (name "/Control_113") (class "Default")
      (node (ref "R96") (pin "1") (pinfunction "1_1") (pintype "passive"))
      (node (ref "RL96") (pin "3") (pintype "passive"))
    )
    (net (code "152") (name "/Control_120") (class "Default")
      (node (ref "R97") (pin "1") (pinfunction "1_1") (pintype "passive"))
      (node (ref "RL97") (pin "3") (pintype "passive"))
    )
    (net (code "153") (name "/Control_121") (class "Default")
      (node (ref "R98") (pin "1") (pinfunction "1_1") (pintype "passive"))
      (node (ref "RL98") (pin "3") (pintype "passive"))
    )
    (net (code "154") (name "/Control_122") (class "Default")
      (node (ref "R99") (pin "1") (pinfunction "1_1") (pintype "passive"))
      (node (ref "RL99") (pin "3") (pintype "passive"))
    )
    (net (code "155") (name "/Control_123") (class "Default")
      (node (ref "R100") (pin "1") (pinfunction "1_1") (pintype "passive"))
      (node (ref "RL100") (pin "3") (pintype "passive"))
    )
    (net (code "156") (name "/Control_124") (class "Default")
      (node (ref "R101") (pin "1") (pinfunction "1_1") (pintype "passive"))
      (node (ref "RL101") (pin "3") (pintype "passive"))
    )
    (net (code "157") (name "/Control_125") (class "Default")
      (node (ref "R102") (pin "1") (pinfunction "1_1") (pintype "passive"))
      (node (ref "RL102") (pin "3") (pintype "passive"))
    )
    (net (code "158") (name "/Control_132") (class "Default")
      (node (ref "R103") (pin "1") (pinfunction "1_1") (pintype "passive"))
      (node (ref "RL103") (pin "3") (pintype "passive"))
    )
    (net (code "159") (name "/Control_133") (class "Default")
      (node (ref "R104") (pin "1") (pinfunction "1_1") (pintype "passive"))
      (node (ref "RL104") (pin "3") (pintype "passive"))
    )
    (net (code "160") (name "/Control_134") (class "Default")
      (node (ref "R105") (pin "1") (pinfunction "1_1") (pintype "passive"))
      (node (ref "RL105") (pin "3") (pintype "passive"))
    )
    (net (code "161") (name "/Control_135") (class "Default")
      (node (ref "R106") (pin "1") (pinfunction "1_1") (pintype "passive"))
      (node (ref "RL106") (pin "3") (pintype "passive"))
    )
    (net (code "162") (name "/Control_136") (class "Default")
      (node (ref "R107") (pin "1") (pinfunction "1_1") (pintype "passive"))
      (node (ref "RL107") (pin "3") (pintype "passive"))
    )
    (net (code "163") (name "/Control_137") (class "Default")
      (node (ref "R108") (pin "1") (pinfunction "1_1") (pintype "passive"))
      (node (ref "RL108") (pin "3") (pintype "passive"))
    )
    (net (code "165") (name "12V") (class "Default")
      (node (ref "D100") (pin "1") (pinfunction "A_1") (pintype "passive"))
      (node (ref "D101") (pin "1") (pinfunction "A_1") (pintype "passive"))
      (node (ref "D102") (pin "1") (pinfunction "A_1") (pintype "passive"))
      (node (ref "D103") (pin "1") (pinfunction "A_1") (pintype "passive"))
      (node (ref "D104") (pin "1") (pinfunction "A_1") (pintype "passive"))
      (node (ref "D105") (pin "1") (pinfunction "A_1") (pintype "passive"))
      (node (ref "D106") (pin "1") (pinfunction "A_1") (pintype "passive"))
      (node (ref "D107") (pin "1") (pinfunction "A_1") (pintype "passive"))
      (node (ref "D108") (pin "1") (pinfunction "A_1") (pintype "passive"))
      (node (ref "D73") (pin "1") (pinfunction "A_1") (pintype "passive"))
      (node (ref "D74") (pin "1") (pinfunction "A_1") (pintype "passive"))
      (node (ref "D75") (pin "1") (pinfunction "A_1") (pintype "passive"))
      (node (ref "D76") (pin "1") (pinfunction "A_1") (pintype "passive"))
      (node (ref "D77") (pin "1") (pinfunction "A_1") (pintype "passive"))
      (node (ref "D78") (pin "1") (pinfunction "A_1") (pintype "passive"))
      (node (ref "D79") (pin "1") (pinfunction "A_1") (pintype "passive"))
      (node (ref "D80") (pin "1") (pinfunction "A_1") (pintype "passive"))
      (node (ref "D81") (pin "1") (pinfunction "A_1") (pintype "passive"))
      (node (ref "D82") (pin "1") (pinfunction "A_1") (pintype "passive"))
      (node (ref "D83") (pin "1") (pinfunction "A_1") (pintype "passive"))
      (node (ref "D84") (pin "1") (pinfunction "A_1") (pintype "passive"))
      (node (ref "D85") (pin "1") (pinfunction "A_1") (pintype "passive"))
      (node (ref "D86") (pin "1") (pinfunction "A_1") (pintype "passive"))
      (node (ref "D87") (pin "1") (pinfunction "A_1") (pintype "passive"))
      (node (ref "D88") (pin "1") (pinfunction "A_1") (pintype "passive"))
      (node (ref "D89") (pin "1") (pinfunction "A_1") (pintype "passive"))
      (node (ref "D90") (pin "1") (pinfunction "A_1") (pintype "passive"))
      (node (ref "D91") (pin "1") (pinfunction "A_1") (pintype "passive"))
      (node (ref "D92") (pin "1") (pinfunction "A_1") (pintype "passive"))
      (node (ref "D93") (pin "1") (pinfunction "A_1") (pintype "passive"))
      (node (ref "D94") (pin "1") (pinfunction "A_1") (pintype "passive"))
      (node (ref "D95") (pin "1") (pinfunction "A_1") (pintype "passive"))
      (node (ref "D96") (pin "1") (pinfunction "A_1") (pintype "passive"))
      (node (ref "D97") (pin "1") (pinfunction "A_1") (pintype "passive"))
      (node (ref "D98") (pin "1") (pinfunction "A_1") (pintype "passive"))
      (node (ref "D99") (pin "1") (pinfunction "A_1") (pintype "passive"))
      (node (ref "RL100") (pin "1") (pintype "passive"))
      (node (ref "RL101") (pin "1") (pintype "passive"))
      (node (ref "RL102") (pin "1") (pintype "passive"))
      (node (ref "RL103") (pin "1") (pintype "passive"))
      (node (ref "RL104") (pin "1") (pintype "passive"))
      (node (ref "RL105") (pin "1") (pintype "passive"))
      (node (ref "RL106") (pin "1") (pintype "passive"))
      (node (ref "RL107") (pin "1") (pintype "passive"))
      (node (ref "RL108") (pin "1") (pintype "passive"))
      (node (ref "RL73") (pin "1") (pintype "passive"))
      (node (ref "RL74") (pin "1") (pintype "passive"))
      (node (ref "RL75") (pin "1") (pintype "passive"))
      (node (ref "RL76") (pin "1") (pintype "passive"))
      (node (ref "RL77") (pin "1") (pintype "passive"))
      (node (ref "RL78") (pin "1") (pintype "passive"))
      (node (ref "RL79") (pin "1") (pintype "passive"))
      (node (ref "RL80") (pin "1") (pintype "passive"))
      (node (ref "RL81") (pin "1") (pintype "passive"))
      (node (ref "RL82") (pin "1") (pintype "passive"))
      (node (ref "RL83") (pin "1") (pintype "passive"))
      (node (ref "RL84") (pin "1") (pintype "passive"))
      (node (ref "RL85") (pin "1") (pintype "passive"))
      (node (ref "RL86") (pin "1") (pintype "passive"))
      (node (ref "RL87") (pin "1") (pintype "passive"))
      (node (ref "RL88") (pin "1") (pintype "passive"))
      (node (ref "RL89") (pin "1") (pintype "passive"))
      (node (ref "RL90") (pin "1") (pintype "passive"))
      (node (ref "RL91") (pin "1") (pintype "passive"))
      (node (ref "RL92") (pin "1") (pintype "passive"))
      (node (ref "RL93") (pin "1") (pintype "passive"))
      (node (ref "RL94") (pin "1") (pintype "passive"))
      (node (ref "RL95") (pin "1") (pintype "passive"))
      (node (ref "RL96") (pin "1") (pintype "passive"))
      (node (ref "RL97") (pin "1") (pintype "passive"))
      (node (ref "RL98") (pin "1") (pintype "passive"))
      (node (ref "RL99") (pin "1") (pintype "passive"))
    )
    (net (code "166") (name "Net-(D73-K)") (class "Default")
      (node (ref "D73") (pin "2") (pinfunction "K_2") (pintype "passive"))
      (node (ref "R73") (pin "2") (pinfunction "2_2") (pintype "passive"))
    )
    (net (code "167") (name "Net-(D74-K)") (class "Default")
      (node (ref "D74") (pin "2") (pinfunction "K_2") (pintype "passive"))
      (node (ref "R74") (pin "2") (pinfunction "2_2") (pintype "passive"))
    )
    (net (code "168") (name "Net-(D75-K)") (class "Default")
      (node (ref "D75") (pin "2") (pinfunction "K_2") (pintype "passive"))
      (node (ref "R75") (pin "2") (pinfunction "2_2") (pintype "passive"))
    )
    (net (code "169") (name "Net-(D76-K)") (class "Default")
      (node (ref "D76") (pin "2") (pinfunction "K_2") (pintype "passive"))
      (node (ref "R76") (pin "2") (pinfunction "2_2") (pintype "passive"))
    )
    (net (code "170") (name "Net-(D77-K)") (class "Default")
      (node (ref "D77") (pin "2") (pinfunction "K_2") (pintype "passive"))
      (node (ref "R77") (pin "2") (pinfunction "2_2") (pintype "passive"))
    )
    (net (code "171") (name "Net-(D78-K)") (class "Default")
      (node (ref "D78") (pin "2") (pinfunction "K_2") (pintype "passive"))
      (node (ref "R78") (pin "2") (pinfunction "2_2") (pintype "passive"))
    )
    (net (code "172") (name "Net-(D79-K)") (class "Default")
      (node (ref "D79") (pin "2") (pinfunction "K_2") (pintype "passive"))
      (node (ref "R79") (pin "2") (pinfunction "2_2") (pintype "passive"))
    )
    (net (code "173") (name "Net-(D80-K)") (class "Default")
      (node (ref "D80") (pin "2") (pinfunction "K_2") (pintype "passive"))
      (node (ref "R80") (pin "2") (pinfunction "2_2") (pintype "passive"))
    )
    (net (code "174") (name "Net-(D81-K)") (class "Default")
      (node (ref "D81") (pin "2") (pinfunction "K_2") (pintype "passive"))
      (node (ref "R81") (pin "2") (pinfunction "2_2") (pintype "passive"))
    )
    (net (code "175") (name "Net-(D82-K)") (class "Default")
      (node (ref "D82") (pin "2") (pinfunction "K_2") (pintype "passive"))
      (node (ref "R82") (pin "2") (pinfunction "2_2") (pintype "passive"))
    )
    (net (code "176") (name "Net-(D83-K)") (class "Default")
      (node (ref "D83") (pin "2") (pinfunction "K_2") (pintype "passive"))
      (node (ref "R83") (pin "2") (pinfunction "2_2") (pintype "passive"))
    )
    (net (code "177") (name "Net-(D84-K)") (class "Default")
      (node (ref "D84") (pin "2") (pinfunction "K_2") (pintype "passive"))
      (node (ref "R84") (pin "2") (pinfunction "2_2") (pintype "passive"))
    )
    (net (code "178") (name "Net-(D85-K)") (class "Default")
      (node (ref "D85") (pin "2") (pinfunction "K_2") (pintype "passive"))
      (node (ref "R85") (pin "2") (pinfunction "2_2") (pintype "passive"))
    )
    (net (code "179") (name "Net-(D86-K)") (class "Default")
      (node (ref "D86") (pin "2") (pinfunction "K_2") (pintype "passive"))
      (node (ref "R86") (pin "2") (pinfunction "2_2") (pintype "passive"))
    )
    (net (code "180") (name "Net-(D87-K)") (class "Default")
      (node (ref "D87") (pin "2") (pinfunction "K_2") (pintype "passive"))
      (node (ref "R87") (pin "2") (pinfunction "2_2") (pintype "passive"))
    )
    (net (code "181") (name "Net-(D88-K)") (class "Default")
      (node (ref "D88") (pin "2") (pinfunction "K_2") (pintype "passive"))
      (node (ref "R88") (pin "2") (pinfunction "2_2") (pintype "passive"))
    )
    (net (code "182") (name "Net-(D89-K)") (class "Default")
      (node (ref "D89") (pin "2") (pinfunction "K_2") (pintype "passive"))
      (node (ref "R89") (pin "2") (pinfunction "2_2") (pintype "passive"))
    )
    (net (code "183") (name "Net-(D90-K)") (class "Default")
      (node (ref "D90") (pin "2") (pinfunction "K_2") (pintype "passive"))
      (node (ref "R90") (pin "2") (pinfunction "2_2") (pintype "passive"))
    )
    (net (code "184") (name "Net-(D91-K)") (class "Default")
      (node (ref "D91") (pin "2") (pinfunction "K_2") (pintype "passive"))
      (node (ref "R91") (pin "2") (pinfunction "2_2") (pintype "passive"))
    )
    (net (code "185") (name "Net-(D92-K)") (class "Default")
      (node (ref "D92") (pin "2") (pinfunction "K_2") (pintype "passive"))
      (node (ref "R92") (pin "2") (pinfunction "2_2") (pintype "passive"))
    )
    (net (code "186") (name "Net-(D93-K)") (class "Default")
      (node (ref "D93") (pin "2") (pinfunction "K_2") (pintype "passive"))
      (node (ref "R93") (pin "2") (pinfunction "2_2") (pintype "passive"))
    )
    (net (code "187") (name "Net-(D94-K)") (class "Default")
      (node (ref "D94") (pin "2") (pinfunction "K_2") (pintype "passive"))
      (node (ref "R94") (pin "2") (pinfunction "2_2") (pintype "passive"))
    )
    (net (code "188") (name "Net-(D95-K)") (class "Default")
      (node (ref "D95") (pin "2") (pinfunction "K_2") (pintype "passive"))
      (node (ref "R95") (pin "2") (pinfunction "2_2") (pintype "passive"))
    )
    (net (code "189") (name "Net-(D96-K)") (class "Default")
      (node (ref "D96") (pin "2") (pinfunction "K_2") (pintype "passive"))
      (node (ref "R96") (pin "2") (pinfunction "2_2") (pintype "passive"))
    )
    (net (code "190") (name "Net-(D97-K)") (class "Default")
      (node (ref "D97") (pin "2") (pinfunction "K_2") (pintype "passive"))
      (node (ref "R97") (pin "2") (pinfunction "2_2") (pintype "passive"))
    )
    (net (code "191") (name "Net-(D98-K)") (class "Default")
      (node (ref "D98") (pin "2") (pinfunction "K_2") (pintype "passive"))
      (node (ref "R98") (pin "2") (pinfunction "2_2") (pintype "passive"))
    )
    (net (code "192") (name "Net-(D99-K)") (class "Default")
      (node (ref "D99") (pin "2") (pinfunction "K_2") (pintype "passive"))
      (node (ref "R99") (pin "2") (pinfunction "2_2") (pintype "passive"))
    )
    (net (code "193") (name "Net-(D100-K)") (class "Default")
      (node (ref "D100") (pin "2") (pinfunction "K_2") (pintype "passive"))
      (node (ref "R100") (pin "2") (pinfunction "2_2") (pintype "passive"))
    )
    (net (code "194") (name "Net-(D101-K)") (class "Default")
      (node (ref "D101") (pin "2") (pinfunction "K_2") (pintype "passive"))
      (node (ref "R101") (pin "2") (pinfunction "2_2") (pintype "passive"))
    )
    (net (code "195") (name "Net-(D102-K)") (class "Default")
      (node (ref "D102") (pin "2") (pinfunction "K_2") (pintype "passive"))
      (node (ref "R102") (pin "2") (pinfunction "2_2") (pintype "passive"))
    )
    (net (code "196") (name "Net-(D103-K)") (class "Default")
      (node (ref "D103") (pin "2") (pinfunction "K_2") (pintype "passive"))
      (node (ref "R103") (pin "2") (pinfunction "2_2") (pintype "passive"))
    )
    (net (code "197") (name "Net-(D104-K)") (class "Default")
      (node (ref "D104") (pin "2") (pinfunction "K_2") (pintype "passive"))
      (node (ref "R104") (pin "2") (pinfunction "2_2") (pintype "passive"))
    )
    (net (code "198") (name "Net-(D105-K)") (class "Default")
      (node (ref "D105") (pin "2") (pinfunction "K_2") (pintype "passive"))
      (node (ref "R105") (pin "2") (pinfunction "2_2") (pintype "passive"))
    )
    (net (code "199") (name "Net-(D106-K)") (class "Default")
      (node (ref "D106") (pin "2") (pinfunction "K_2") (pintype "passive"))
      (node (ref "R106") (pin "2") (pinfunction "2_2") (pintype "passive"))
    )
    (net (code "200") (name "Net-(D107-K)") (class "Default")
      (node (ref "D107") (pin "2") (pinfunction "K_2") (pintype "passive"))
      (node (ref "R107") (pin "2") (pinfunction "2_2") (pintype "passive"))
    )
    (net (code "201") (name "Net-(D108-K)") (class "Default")
      (node (ref "D108") (pin "2") (pinfunction "K_2") (pintype "passive"))
      (node (ref "R108") (pin "2") (pinfunction "2_2") (pintype "passive"))
    )
    (net (code "202") (name "unconnected-(RL73-Pad4)") (class "Default")
      (node (ref "RL73") (pin "4") (pintype "passive"))
    )
    (net (code "203") (name "unconnected-(RL73-Pad5)") (class "Default")
      (node (ref "RL73") (pin "5") (pintype "passive"))
    )
    (net (code "204") (name "unconnected-(RL73-Pad6)") (class "Default")
      (node (ref "RL73") (pin "6") (pintype "passive"))
    )
    (net (code "205") (name "unconnected-(RL74-Pad4)") (class "Default")
      (node (ref "RL74") (pin "4") (pintype "passive"))
    )
    (net (code "206") (name "unconnected-(RL74-Pad5)") (class "Default")
      (node (ref "RL74") (pin "5") (pintype "passive"))
    )
    (net (code "207") (name "unconnected-(RL74-Pad6)") (class "Default")
      (node (ref "RL74") (pin "6") (pintype "passive"))
    )
    (net (code "208") (name "unconnected-(RL75-Pad4)") (class "Default")
      (node (ref "RL75") (pin "4") (pintype "passive"))
    )
    (net (code "209") (name "unconnected-(RL75-Pad5)") (class "Default")
      (node (ref "RL75") (pin "5") (pintype "passive"))
    )
    (net (code "210") (name "unconnected-(RL75-Pad6)") (class "Default")
      (node (ref "RL75") (pin "6") (pintype "passive"))
    )
    (net (code "211") (name "unconnected-(RL76-Pad4)") (class "Default")
      (node (ref "RL76") (pin "4") (pintype "passive"))
    )
    (net (code "212") (name "unconnected-(RL76-Pad5)") (class "Default")
      (node (ref "RL76") (pin "5") (pintype "passive"))
    )
    (net (code "213") (name "unconnected-(RL76-Pad6)") (class "Default")
      (node (ref "RL76") (pin "6") (pintype "passive"))
    )
    (net (code "214") (name "unconnected-(RL77-Pad4)") (class "Default")
      (node (ref "RL77") (pin "4") (pintype "passive"))
    )
    (net (code "215") (name "unconnected-(RL77-Pad5)") (class "Default")
      (node (ref "RL77") (pin "5") (pintype "passive"))
    )
    (net (code "216") (name "unconnected-(RL77-Pad6)") (class "Default")
      (node (ref "RL77") (pin "6") (pintype "passive"))
    )
    (net (code "217") (name "unconnected-(RL78-Pad4)") (class "Default")
      (node (ref "RL78") (pin "4") (pintype "passive"))
    )
    (net (code "218") (name "unconnected-(RL78-Pad5)") (class "Default")
      (node (ref "RL78") (pin "5") (pintype "passive"))
    )
    (net (code "219") (name "unconnected-(RL78-Pad6)") (class "Default")
      (node (ref "RL78") (pin "6") (pintype "passive"))
    )
    (net (code "220") (name "unconnected-(RL79-Pad4)") (class "Default")
      (node (ref "RL79") (pin "4") (pintype "passive"))
    )
    (net (code "221") (name "unconnected-(RL79-Pad5)") (class "Default")
      (node (ref "RL79") (pin "5") (pintype "passive"))
    )
    (net (code "222") (name "unconnected-(RL79-Pad6)") (class "Default")
      (node (ref "RL79") (pin "6") (pintype "passive"))
    )
    (net (code "223") (name "unconnected-(RL80-Pad4)") (class "Default")
      (node (ref "RL80") (pin "4") (pintype "passive"))
    )
    (net (code "224") (name "unconnected-(RL80-Pad5)") (class "Default")
      (node (ref "RL80") (pin "5") (pintype "passive"))
    )
    (net (code "225") (name "unconnected-(RL80-Pad6)") (class "Default")
      (node (ref "RL80") (pin "6") (pintype "passive"))
    )
    (net (code "226") (name "unconnected-(RL81-Pad4)") (class "Default")
      (node (ref "RL81") (pin "4") (pintype "passive"))
    )
    (net (code "227") (name "unconnected-(RL81-Pad5)") (class "Default")
      (node (ref "RL81") (pin "5") (pintype "passive"))
    )
    (net (code "228") (name "unconnected-(RL81-Pad6)") (class "Default")
      (node (ref "RL81") (pin "6") (pintype "passive"))
    )
    (net (code "229") (name "unconnected-(RL82-Pad4)") (class "Default")
      (node (ref "RL82") (pin "4") (pintype "passive"))
    )
    (net (code "230") (name "unconnected-(RL82-Pad5)") (class "Default")
      (node (ref "RL82") (pin "5") (pintype "passive"))
    )
    (net (code "231") (name "unconnected-(RL82-Pad6)") (class "Default")
      (node (ref "RL82") (pin "6") (pintype "passive"))
    )
    (net (code "232") (name "unconnected-(RL83-Pad4)") (class "Default")
      (node (ref "RL83") (pin "4") (pintype "passive"))
    )
    (net (code "233") (name "unconnected-(RL83-Pad5)") (class "Default")
      (node (ref "RL83") (pin "5") (pintype "passive"))
    )
    (net (code "234") (name "unconnected-(RL83-Pad6)") (class "Default")
      (node (ref "RL83") (pin "6") (pintype "passive"))
    )
    (net (code "235") (name "unconnected-(RL84-Pad4)") (class "Default")
      (node (ref "RL84") (pin "4") (pintype "passive"))
    )
    (net (code "236") (name "unconnected-(RL84-Pad5)") (class "Default")
      (node (ref "RL84") (pin "5") (pintype "passive"))
    )
    (net (code "237") (name "unconnected-(RL84-Pad6)") (class "Default")
      (node (ref "RL84") (pin "6") (pintype "passive"))
    )
    (net (code "238") (name "unconnected-(RL85-Pad4)") (class "Default")
      (node (ref "RL85") (pin "4") (pintype "passive"))
    )
    (net (code "239") (name "unconnected-(RL85-Pad5)") (class "Default")
      (node (ref "RL85") (pin "5") (pintype "passive"))
    )
    (net (code "240") (name "unconnected-(RL85-Pad6)") (class "Default")
      (node (ref "RL85") (pin "6") (pintype "passive"))
    )
    (net (code "241") (name "unconnected-(RL86-Pad4)") (class "Default")
      (node (ref "RL86") (pin "4") (pintype "passive"))
    )
    (net (code "242") (name "unconnected-(RL86-Pad5)") (class "Default")
      (node (ref "RL86") (pin "5") (pintype "passive"))
    )
    (net (code "243") (name "unconnected-(RL86-Pad6)") (class "Default")
      (node (ref "RL86") (pin "6") (pintype "passive"))
    )
    (net (code "244") (name "unconnected-(RL87-Pad4)") (class "Default")
      (node (ref "RL87") (pin "4") (pintype "passive"))
    )
    (net (code "245") (name "unconnected-(RL87-Pad5)") (class "Default")
      (node (ref "RL87") (pin "5") (pintype "passive"))
    )
    (net (code "246") (name "unconnected-(RL87-Pad6)") (class "Default")
      (node (ref "RL87") (pin "6") (pintype "passive"))
    )
    (net (code "247") (name "unconnected-(RL88-Pad4)") (class "Default")
      (node (ref "RL88") (pin "4") (pintype "passive"))
    )
    (net (code "248") (name "unconnected-(RL88-Pad5)") (class "Default")
      (node (ref "RL88") (pin "5") (pintype "passive"))
    )
    (net (code "249") (name "unconnected-(RL88-Pad6)") (class "Default")
      (node (ref "RL88") (pin "6") (pintype "passive"))
    )
    (net (code "250") (name "unconnected-(RL89-Pad4)") (class "Default")
      (node (ref "RL89") (pin "4") (pintype "passive"))
    )
    (net (code "251") (name "unconnected-(RL89-Pad5)") (class "Default")
      (node (ref "RL89") (pin "5") (pintype "passive"))
    )
    (net (code "252") (name "unconnected-(RL89-Pad6)") (class "Default")
      (node (ref "RL89") (pin "6") (pintype "passive"))
    )
    (net (code "253") (name "unconnected-(RL90-Pad4)") (class "Default")
      (node (ref "RL90") (pin "4") (pintype "passive"))
    )
    (net (code "254") (name "unconnected-(RL90-Pad5)") (class "Default")
      (node (ref "RL90") (pin "5") (pintype "passive"))
    )
    (net (code "255") (name "unconnected-(RL90-Pad6)") (class "Default")
      (node (ref "RL90") (pin "6") (pintype "passive"))
    )
    (net (code "256") (name "unconnected-(RL91-Pad4)") (class "Default")
      (node (ref "RL91") (pin "4") (pintype "passive"))
    )
    (net (code "257") (name "unconnected-(RL91-Pad5)") (class "Default")
      (node (ref "RL91") (pin "5") (pintype "passive"))
    )
    (net (code "258") (name "unconnected-(RL91-Pad6)") (class "Default")
      (node (ref "RL91") (pin "6") (pintype "passive"))
    )
    (net (code "259") (name "unconnected-(RL92-Pad4)") (class "Default")
      (node (ref "RL92") (pin "4") (pintype "passive"))
    )
    (net (code "260") (name "unconnected-(RL92-Pad5)") (class "Default")
      (node (ref "RL92") (pin "5") (pintype "passive"))
    )
    (net (code "261") (name "unconnected-(RL92-Pad6)") (class "Default")
      (node (ref "RL92") (pin "6") (pintype "passive"))
    )
    (net (code "262") (name "unconnected-(RL93-Pad4)") (class "Default")
      (node (ref "RL93") (pin "4") (pintype "passive"))
    )
    (net (code "263") (name "unconnected-(RL93-Pad5)") (class "Default")
      (node (ref "RL93") (pin "5") (pintype "passive"))
    )
    (net (code "264") (name "unconnected-(RL93-Pad6)") (class "Default")
      (node (ref "RL93") (pin "6") (pintype "passive"))
    )
    (net (code "265") (name "unconnected-(RL94-Pad4)") (class "Default")
      (node (ref "RL94") (pin "4") (pintype "passive"))
    )
    (net (code "266") (name "unconnected-(RL94-Pad5)") (class "Default")
      (node (ref "RL94") (pin "5") (pintype "passive"))
    )
    (net (code "267") (name "unconnected-(RL94-Pad6)") (class "Default")
      (node (ref "RL94") (pin "6") (pintype "passive"))
    )
    (net (code "268") (name "unconnected-(RL95-Pad4)") (class "Default")
      (node (ref "RL95") (pin "4") (pintype "passive"))
    )
    (net (code "269") (name "unconnected-(RL95-Pad5)") (class "Default")
      (node (ref "RL95") (pin "5") (pintype "passive"))
    )
    (net (code "270") (name "unconnected-(RL95-Pad6)") (class "Default")
      (node (ref "RL95") (pin "6") (pintype "passive"))
    )
    (net (code "271") (name "unconnected-(RL96-Pad4)") (class "Default")
      (node (ref "RL96") (pin "4") (pintype "passive"))
    )
    (net (code "272") (name "unconnected-(RL96-Pad5)") (class "Default")
      (node (ref "RL96") (pin "5") (pintype "passive"))
    )
    (net (code "273") (name "unconnected-(RL96-Pad6)") (class "Default")
      (node (ref "RL96") (pin "6") (pintype "passive"))
    )
    (net (code "274") (name "unconnected-(RL97-Pad4)") (class "Default")
      (node (ref "RL97") (pin "4") (pintype "passive"))
    )
    (net (code "275") (name "unconnected-(RL97-Pad5)") (class "Default")
      (node (ref "RL97") (pin "5") (pintype "passive"))
    )
    (net (code "276") (name "unconnected-(RL97-Pad6)") (class "Default")
      (node (ref "RL97") (pin "6") (pintype "passive"))
    )
    (net (code "277") (name "unconnected-(RL98-Pad4)") (class "Default")
      (node (ref "RL98") (pin "4") (pintype "passive"))
    )
    (net (code "278") (name "unconnected-(RL98-Pad5)") (class "Default")
      (node (ref "RL98") (pin "5") (pintype "passive"))
    )
    (net (code "279") (name "unconnected-(RL98-Pad6)") (class "Default")
      (node (ref "RL98") (pin "6") (pintype "passive"))
    )
    (net (code "280") (name "unconnected-(RL99-Pad4)") (class "Default")
      (node (ref "RL99") (pin "4") (pintype "passive"))
    )
    (net (code "281") (name "unconnected-(RL99-Pad5)") (class "Default")
      (node (ref "RL99") (pin "5") (pintype "passive"))
    )
    (net (code "282") (name "unconnected-(RL99-Pad6)") (class "Default")
      (node (ref "RL99") (pin "6") (pintype "passive"))
    )
    (net (code "283") (name "unconnected-(RL100-Pad4)") (class "Default")
      (node (ref "RL100") (pin "4") (pintype "passive"))
    )
    (net (code "284") (name "unconnected-(RL100-Pad5)") (class "Default")
      (node (ref "RL100") (pin "5") (pintype "passive"))
    )
    (net (code "285") (name "unconnected-(RL100-Pad6)") (class "Default")
      (node (ref "RL100") (pin "6") (pintype "passive"))
    )
    (net (code "286") (name "unconnected-(RL101-Pad4)") (class "Default")
      (node (ref "RL101") (pin "4") (pintype "passive"))
    )
    (net (code "287") (name "unconnected-(RL101-Pad5)") (class "Default")
      (node (ref "RL101") (pin "5") (pintype "passive"))
    )
    (net (code "288") (name "unconnected-(RL101-Pad6)") (class "Default")
      (node (ref "RL101") (pin "6") (pintype "passive"))
    )
    (net (code "289") (name "unconnected-(RL102-Pad4)") (class "Default")
      (node (ref "RL102") (pin "4") (pintype "passive"))
    )
    (net (code "290") (name "unconnected-(RL102-Pad5)") (class "Default")
      (node (ref "RL102") (pin "5") (pintype "passive"))
    )
    (net (code "291") (name "unconnected-(RL102-Pad6)") (class "Default")
      (node (ref "RL102") (pin "6") (pintype "passive"))
    )
    (net (code "292") (name "unconnected-(RL103-Pad4)") (class "Default")
      (node (ref "RL103") (pin "4") (pintype "passive"))
    )
    (net (code "293") (name "unconnected-(RL103-Pad5)") (class "Default")
      (node (ref "RL103") (pin "5") (pintype "passive"))
    )
    (net (code "294") (name "unconnected-(RL103-Pad6)") (class "Default")
      (node (ref "RL103") (pin "6") (pintype "passive"))
    )
    (net (code "295") (name "unconnected-(RL104-Pad4)") (class "Default")
      (node (ref "RL104") (pin "4") (pintype "passive"))
    )
    (net (code "296") (name "unconnected-(RL104-Pad5)") (class "Default")
      (node (ref "RL104") (pin "5") (pintype "passive"))
    )
    (net (code "297") (name "unconnected-(RL104-Pad6)") (class "Default")
      (node (ref "RL104") (pin "6") (pintype "passive"))
    )
    (net (code "298") (name "unconnected-(RL105-Pad4)") (class "Default")
      (node (ref "RL105") (pin "4") (pintype "passive"))
    )
    (net (code "299") (name "unconnected-(RL105-Pad5)") (class "Default")
      (node (ref "RL105") (pin "5") (pintype "passive"))
    )
    (net (code "300") (name "unconnected-(RL105-Pad6)") (class "Default")
      (node (ref "RL105") (pin "6") (pintype "passive"))
    )
    (net (code "301") (name "unconnected-(RL106-Pad4)") (class "Default")
      (node (ref "RL106") (pin "4") (pintype "passive"))
    )
    (net (code "302") (name "unconnected-(RL106-Pad5)") (class "Default")
      (node (ref "RL106") (pin "5") (pintype "passive"))
    )
    (net (code "303") (name "unconnected-(RL106-Pad6)") (class "Default")
      (node (ref "RL106") (pin "6") (pintype "passive"))
    )
    (net (code "304") (name "unconnected-(RL107-Pad4)") (class "Default")
      (node (ref "RL107") (pin "4") (pintype "passive"))
    )
    (net (code "305") (name "unconnected-(RL107-Pad5)") (class "Default")
      (node (ref "RL107") (pin "5") (pintype "passive"))
    )
    (net (code "306") (name "unconnected-(RL107-Pad6)") (class "Default")
      (node (ref "RL107") (pin "6") (pintype "passive"))
    )
    (net (code "307") (name "unconnected-(RL108-Pad4)") (class "Default")
      (node (ref "RL108") (pin "4") (pintype "passive"))
    )
    (net (code "308") (name "unconnected-(RL108-Pad5)") (class "Default")
      (node (ref "RL108") (pin "5") (pintype "passive"))
    )
    (net (code "309") (name "unconnected-(RL108-Pad6)") (class "Default")
      (node (ref "RL108") (pin "6") (pintype "passive"))
    )
  )
)
